# TRV_MRF49_U_V1_1_F.net
KiCad netlist of a schematic drawn in EAGLE
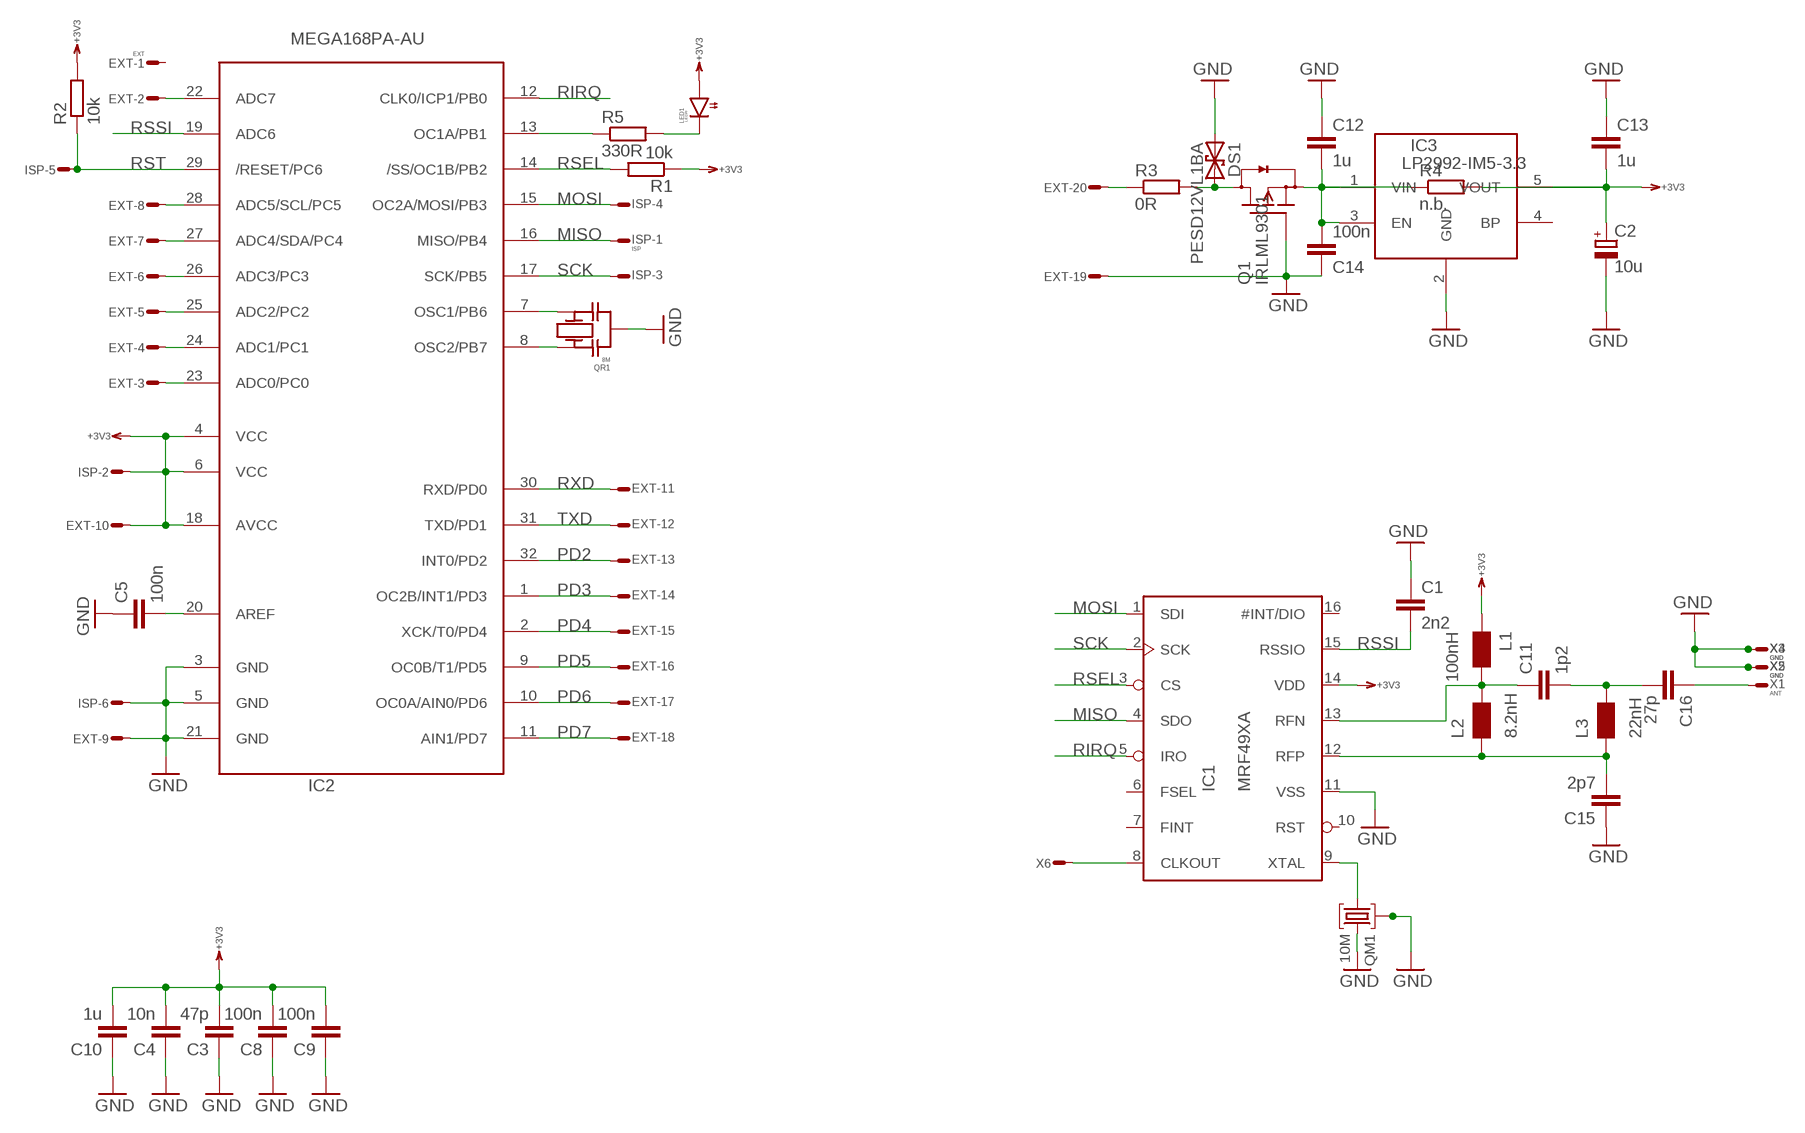
[diagram p0: schematic, sheet 1]

(export (version "E")
  (design (tool "Eeschema 10.0.6"))
  (components
    (comp (ref "C1")
      (value "2n2")
      (footprint "eagle-import:0603")
      (libsource (lib "eagle-import") (part "C0603"))
    )
    (comp (ref "C2")
      (value "10u")
      (footprint "eagle-import:SMC_B")
      (libsource (lib "eagle-import") (part "C_POLSMCB"))
    )
    (comp (ref "C3")
      (value "47p")
      (footprint "eagle-import:0603")
      (libsource (lib "eagle-import") (part "C0603"))
    )
    (comp (ref "C4")
      (value "10n")
      (footprint "eagle-import:0603")
      (libsource (lib "eagle-import") (part "C0603"))
    )
    (comp (ref "C5")
      (value "100n")
      (footprint "eagle-import:0603")
      (libsource (lib "eagle-import") (part "C0603"))
    )
    (comp (ref "C8")
      (value "100n")
      (footprint "eagle-import:0603")
      (libsource (lib "eagle-import") (part "C0603"))
    )
    (comp (ref "C9")
      (value "100n")
      (footprint "eagle-import:0603")
      (libsource (lib "eagle-import") (part "C0603"))
    )
    (comp (ref "C10")
      (value "1u")
      (footprint "eagle-import:0603")
      (libsource (lib "eagle-import") (part "C0603"))
    )
    (comp (ref "C11")
      (value "1p2")
      (footprint "eagle-import:0603")
      (libsource (lib "eagle-import") (part "C0603"))
    )
    (comp (ref "C12")
      (value "1u")
      (footprint "eagle-import:0603")
      (libsource (lib "eagle-import") (part "C0603"))
    )
    (comp (ref "C13")
      (value "1u")
      (footprint "eagle-import:0603")
      (libsource (lib "eagle-import") (part "C0603"))
    )
    (comp (ref "C14")
      (value "100n")
      (footprint "eagle-import:0603")
      (libsource (lib "eagle-import") (part "C0603"))
    )
    (comp (ref "C15")
      (value "2p7")
      (footprint "eagle-import:0603")
      (libsource (lib "eagle-import") (part "C0603"))
    )
    (comp (ref "C16")
      (value "27p")
      (footprint "eagle-import:0603")
      (libsource (lib "eagle-import") (part "C0603"))
    )
    (comp (ref "DS1")
      (value "PESD12VL1BA")
      (footprint "eagle-import:SOD323")
      (libsource (lib "eagle-import") (part "TVS-U323"))
    )
    (comp (ref "EXT")
      (value "EXT")
      (footprint "eagle-import:ML20S")
      (libsource (lib "eagle-import") (part "ML20?ES"))
    )
    (comp (ref "IC1")
      (value "MRF49XA")
      (footprint "eagle-import:TSSOP16")
      (libsource (lib "eagle-import") (part "MRF49XA"))
    )
    (comp (ref "IC2")
      (value "MEGA168PA-AU")
      (footprint "eagle-import:TQFP32-08")
      (libsource (lib "eagle-import") (part "MEGA168PA"))
    )
    (comp (ref "IC3")
      (value "LP2992-IM5-3.3")
      (footprint "eagle-import:SOT23-5")
      (libsource (lib "eagle-import") (part "LDO"))
    )
    (comp (ref "ISP")
      (value "ISP")
      (footprint "eagle-import:ML6S")
      (libsource (lib "eagle-import") (part "ML6ES"))
    )
    (comp (ref "L1")
      (value "100nH")
      (footprint "eagle-import:0603")
      (libsource (lib "eagle-import") (part "L0603"))
    )
    (comp (ref "L2")
      (value "8.2nH")
      (footprint "eagle-import:0603")
      (libsource (lib "eagle-import") (part "L0603"))
    )
    (comp (ref "L3")
      (value "22nH")
      (footprint "eagle-import:0603")
      (libsource (lib "eagle-import") (part "L0603"))
    )
    (comp (ref "LED1")
      (value "LEDR")
      (footprint "eagle-import:0603")
      (libsource (lib "eagle-import") (part "LED0603"))
    )
    (comp (ref "Q1")
      (value "IRLML9301")
      (footprint "eagle-import:SOT23")
      (libsource (lib "eagle-import") (part "FET-PDSOT23"))
    )
    (comp (ref "QM1")
      (value "10M")
      (footprint "eagle-import:ABM3C")
      (libsource (lib "eagle-import") (part "QM5X3.2"))
    )
    (comp (ref "QR1")
      (value "8M")
      (footprint "eagle-import:CR")
      (libsource (lib "eagle-import") (part "QRCR"))
    )
    (comp (ref "R1")
      (value "10k")
      (footprint "eagle-import:0603")
      (libsource (lib "eagle-import") (part "R0603"))
    )
    (comp (ref "R2")
      (value "10k")
      (footprint "eagle-import:0603")
      (libsource (lib "eagle-import") (part "R0603"))
    )
    (comp (ref "R3")
      (value "0R")
      (footprint "eagle-import:0603")
      (libsource (lib "eagle-import") (part "R0603"))
    )
    (comp (ref "R4")
      (value "n.b.")
      (footprint "eagle-import:0603")
      (libsource (lib "eagle-import") (part "R0603"))
    )
    (comp (ref "R5")
      (value "330R")
      (footprint "eagle-import:0603")
      (libsource (lib "eagle-import") (part "R0603"))
    )
    (comp (ref "X1")
      (value "ANT")
      (footprint "eagle-import:S2.54_1.27")
      (libsource (lib "eagle-import") (part "WIREPADS2.54/1.27"))
    )
    (comp (ref "X2")
      (value "GND")
      (footprint "eagle-import:S2.54_1.27")
      (libsource (lib "eagle-import") (part "WIREPADS2.54/1.27"))
    )
    (comp (ref "X3")
      (value "GND")
      (footprint "eagle-import:S2.54_1.27")
      (libsource (lib "eagle-import") (part "WIREPADS2.54/1.27"))
    )
    (comp (ref "X4")
      (value "GND")
      (footprint "eagle-import:S2.54_1.27")
      (libsource (lib "eagle-import") (part "WIREPADS2.54/1.27"))
    )
    (comp (ref "X5")
      (value "GND")
      (footprint "eagle-import:S2.54_1.27")
      (libsource (lib "eagle-import") (part "WIREPADS2.54/1.27"))
    )
    (comp (ref "X6")
      (value "WIREPADR")
      (footprint "eagle-import:S1.27R")
      (libsource (lib "eagle-import") (part "WIREPADR"))
    )
  )
  (nets
    (net (code "1") (name "+3V3") (class "Default")
      (node (ref "C10") (pin "2") (pinfunction "2_2") (pintype "passive"))
      (node (ref "C13") (pin "2") (pinfunction "2_2") (pintype "passive"))
      (node (ref "C2") (pin "+") (pinfunction "+_+") (pintype "passive"))
      (node (ref "C3") (pin "2") (pinfunction "2_2") (pintype "passive"))
      (node (ref "C4") (pin "2") (pinfunction "2_2") (pintype "passive"))
      (node (ref "C8") (pin "2") (pinfunction "2_2") (pintype "passive"))
      (node (ref "C9") (pin "2") (pinfunction "2_2") (pintype "passive"))
      (node (ref "EXT") (pin "10") (pinfunction "S_10") (pintype "passive"))
      (node (ref "IC1") (pin "14") (pinfunction "VDD_14") (pintype "input"))
      (node (ref "IC2") (pin "18") (pinfunction "AVCC_18") (pintype "bidirectional"))
      (node (ref "IC2") (pin "4") (pinfunction "VCC_4") (pintype "bidirectional"))
      (node (ref "IC2") (pin "6") (pinfunction "VCC_6") (pintype "bidirectional"))
      (node (ref "IC3") (pin "5") (pinfunction "VOUT_5") (pintype "bidirectional"))
      (node (ref "ISP") (pin "2") (pinfunction "S_2") (pintype "passive"))
      (node (ref "L1") (pin "1") (pinfunction "1_1") (pintype "passive"))
      (node (ref "LED1") (pin "1") (pinfunction "A_1") (pintype "bidirectional"))
      (node (ref "R1") (pin "1") (pinfunction "1_1") (pintype "passive"))
      (node (ref "R2") (pin "2") (pinfunction "2_2") (pintype "passive"))
      (node (ref "R4") (pin "2") (pinfunction "2_2") (pintype "passive"))
    )
    (net (code "2") (name "/MISO") (class "Default")
      (node (ref "IC1") (pin "4") (pinfunction "SDO_4") (pintype "output"))
      (node (ref "IC2") (pin "16") (pinfunction "MISO/PB4_16") (pintype "bidirectional"))
      (node (ref "ISP") (pin "1") (pinfunction "S_1") (pintype "passive"))
    )
    (net (code "3") (name "/MOSI") (class "Default")
      (node (ref "IC1") (pin "1") (pinfunction "SDI_1") (pintype "input"))
      (node (ref "IC2") (pin "15") (pinfunction "OC2A/MOSI/PB3_15") (pintype "bidirectional"))
      (node (ref "ISP") (pin "4") (pinfunction "S_4") (pintype "passive"))
    )
    (net (code "4") (name "/PD2") (class "Default")
      (node (ref "EXT") (pin "13") (pinfunction "S_13") (pintype "passive"))
      (node (ref "IC2") (pin "32") (pinfunction "INT0/PD2_32") (pintype "bidirectional"))
    )
    (net (code "5") (name "/PD3") (class "Default")
      (node (ref "EXT") (pin "14") (pinfunction "S_14") (pintype "passive"))
      (node (ref "IC2") (pin "1") (pinfunction "OC2B/INT1/PD3_1") (pintype "bidirectional"))
    )
    (net (code "6") (name "/PD4") (class "Default")
      (node (ref "EXT") (pin "15") (pinfunction "S_15") (pintype "passive"))
      (node (ref "IC2") (pin "2") (pinfunction "XCK/T0/PD4_2") (pintype "bidirectional"))
    )
    (net (code "7") (name "/PD5") (class "Default")
      (node (ref "EXT") (pin "16") (pinfunction "S_16") (pintype "passive"))
      (node (ref "IC2") (pin "9") (pinfunction "OC0B/T1/PD5_9") (pintype "bidirectional"))
    )
    (net (code "8") (name "/PD6") (class "Default")
      (node (ref "EXT") (pin "17") (pinfunction "S_17") (pintype "passive"))
      (node (ref "IC2") (pin "10") (pinfunction "OC0A/AIN0/PD6_10") (pintype "bidirectional"))
    )
    (net (code "9") (name "/PD7") (class "Default")
      (node (ref "EXT") (pin "18") (pinfunction "S_18") (pintype "passive"))
      (node (ref "IC2") (pin "11") (pinfunction "AIN1/PD7_11") (pintype "bidirectional"))
    )
    (net (code "10") (name "/RIRQ") (class "Default")
      (node (ref "IC1") (pin "5") (pinfunction "IRO_5") (pintype "output"))
      (node (ref "IC2") (pin "12") (pinfunction "CLK0/ICP1/PB0_12") (pintype "bidirectional"))
    )
    (net (code "11") (name "/RSEL") (class "Default")
      (node (ref "IC1") (pin "3") (pinfunction "CS_3") (pintype "input"))
      (node (ref "IC2") (pin "14") (pinfunction "/SS/OC1B/PB2_14") (pintype "bidirectional"))
      (node (ref "R1") (pin "2") (pinfunction "2_2") (pintype "passive"))
    )
    (net (code "12") (name "/RSSI") (class "Default")
      (node (ref "C1") (pin "2") (pinfunction "2_2") (pintype "passive"))
      (node (ref "IC1") (pin "15") (pinfunction "RSSIO_15") (pintype "bidirectional"))
      (node (ref "IC2") (pin "19") (pinfunction "ADC6_19") (pintype "bidirectional"))
    )
    (net (code "13") (name "/RST") (class "Default")
      (node (ref "IC2") (pin "29") (pinfunction "/RESET/PC6_29") (pintype "bidirectional"))
      (node (ref "ISP") (pin "5") (pinfunction "S_5") (pintype "passive"))
      (node (ref "R2") (pin "1") (pinfunction "1_1") (pintype "passive"))
    )
    (net (code "14") (name "/RXD") (class "Default")
      (node (ref "EXT") (pin "11") (pinfunction "S_11") (pintype "passive"))
      (node (ref "IC2") (pin "30") (pinfunction "RXD/PD0_30") (pintype "bidirectional"))
    )
    (net (code "15") (name "/SCK") (class "Default")
      (node (ref "IC1") (pin "2") (pinfunction "SCK_2") (pintype "input"))
      (node (ref "IC2") (pin "17") (pinfunction "SCK/PB5_17") (pintype "bidirectional"))
      (node (ref "ISP") (pin "3") (pinfunction "S_3") (pintype "passive"))
    )
    (net (code "16") (name "/TXD") (class "Default")
      (node (ref "EXT") (pin "12") (pinfunction "S_12") (pintype "passive"))
      (node (ref "IC2") (pin "31") (pinfunction "TXD/PD1_31") (pintype "bidirectional"))
    )
    (net (code "17") (name "GND") (class "Default")
      (node (ref "C1") (pin "1") (pinfunction "1_1") (pintype "passive"))
      (node (ref "C10") (pin "1") (pinfunction "1_1") (pintype "passive"))
      (node (ref "C12") (pin "1") (pinfunction "1_1") (pintype "passive"))
      (node (ref "C13") (pin "1") (pinfunction "1_1") (pintype "passive"))
      (node (ref "C14") (pin "1") (pinfunction "1_1") (pintype "passive"))
      (node (ref "C15") (pin "1") (pinfunction "1_1") (pintype "passive"))
      (node (ref "C2") (pin "-") (pinfunction "-_-") (pintype "passive"))
      (node (ref "C3") (pin "1") (pinfunction "1_1") (pintype "passive"))
      (node (ref "C4") (pin "1") (pinfunction "1_1") (pintype "passive"))
      (node (ref "C5") (pin "1") (pinfunction "1_1") (pintype "passive"))
      (node (ref "C8") (pin "1") (pinfunction "1_1") (pintype "passive"))
      (node (ref "C9") (pin "1") (pinfunction "1_1") (pintype "passive"))
      (node (ref "DS1") (pin "A") (pinfunction "1_A") (pintype "passive"))
      (node (ref "EXT") (pin "19") (pinfunction "S_19") (pintype "passive"))
      (node (ref "EXT") (pin "9") (pinfunction "S_9") (pintype "passive"))
      (node (ref "IC1") (pin "11") (pinfunction "VSS_11") (pintype "input"))
      (node (ref "IC2") (pin "21") (pinfunction "GND_21") (pintype "bidirectional"))
      (node (ref "IC2") (pin "3") (pinfunction "GND_3") (pintype "bidirectional"))
      (node (ref "IC2") (pin "5") (pinfunction "GND_5") (pintype "bidirectional"))
      (node (ref "IC3") (pin "2") (pinfunction "GND_2") (pintype "bidirectional"))
      (node (ref "ISP") (pin "6") (pinfunction "S_6") (pintype "passive"))
      (node (ref "Q1") (pin "1") (pinfunction "G_1") (pintype "passive"))
      (node (ref "QM1") (pin "P$2") (pinfunction "M1_P$2") (pintype "passive"))
      (node (ref "QM1") (pin "P$3") (pinfunction "2_P$3") (pintype "passive"))
      (node (ref "QM1") (pin "P$4") (pinfunction "M2_P$4") (pintype "passive"))
      (node (ref "QR1") (pin "M") (pinfunction "M_M") (pintype "passive"))
      (node (ref "X2") (pin "1") (pinfunction "S_1") (pintype "passive"))
      (node (ref "X3") (pin "1") (pinfunction "S_1") (pintype "passive"))
      (node (ref "X4") (pin "1") (pinfunction "S_1") (pintype "passive"))
      (node (ref "X5") (pin "1") (pinfunction "S_1") (pintype "passive"))
    )
    (net (code "18") (name "Net-(C11-Pad2)") (class "Default")
      (node (ref "C11") (pin "2") (pinfunction "2_2") (pintype "passive"))
      (node (ref "C16") (pin "2") (pinfunction "2_2") (pintype "passive"))
      (node (ref "L3") (pin "2") (pinfunction "2_2") (pintype "passive"))
    )
    (net (code "19") (name "Net-(DS1-2)") (class "Default")
      (node (ref "DS1") (pin "C") (pinfunction "2_C") (pintype "passive"))
      (node (ref "Q1") (pin "3") (pinfunction "D_3") (pintype "passive"))
      (node (ref "R3") (pin "2") (pinfunction "2_2") (pintype "passive"))
    )
    (net (code "20") (name "Net-(EXTL-S)") (class "Default")
      (node (ref "EXT") (pin "2") (pinfunction "S_2") (pintype "passive"))
      (node (ref "IC2") (pin "22") (pinfunction "ADC7_22") (pintype "bidirectional"))
    )
    (net (code "21") (name "Net-(EXTM-S)") (class "Default")
      (node (ref "EXT") (pin "20") (pinfunction "S_20") (pintype "passive"))
      (node (ref "R3") (pin "1") (pinfunction "1_1") (pintype "passive"))
    )
    (net (code "22") (name "Net-(EXTN-S)") (class "Default")
      (node (ref "EXT") (pin "3") (pinfunction "S_3") (pintype "passive"))
      (node (ref "IC2") (pin "23") (pinfunction "ADC0/PC0_23") (pintype "bidirectional"))
    )
    (net (code "23") (name "Net-(EXTO-S)") (class "Default")
      (node (ref "EXT") (pin "4") (pinfunction "S_4") (pintype "passive"))
      (node (ref "IC2") (pin "24") (pinfunction "ADC1/PC1_24") (pintype "bidirectional"))
    )
    (net (code "24") (name "Net-(EXTP-S)") (class "Default")
      (node (ref "EXT") (pin "5") (pinfunction "S_5") (pintype "passive"))
      (node (ref "IC2") (pin "25") (pinfunction "ADC2/PC2_25") (pintype "bidirectional"))
    )
    (net (code "25") (name "Net-(EXTQ-S)") (class "Default")
      (node (ref "EXT") (pin "6") (pinfunction "S_6") (pintype "passive"))
      (node (ref "IC2") (pin "26") (pinfunction "ADC3/PC3_26") (pintype "bidirectional"))
    )
    (net (code "26") (name "Net-(EXTR-S)") (class "Default")
      (node (ref "EXT") (pin "7") (pinfunction "S_7") (pintype "passive"))
      (node (ref "IC2") (pin "27") (pinfunction "ADC4/SDA/PC4_27") (pintype "bidirectional"))
    )
    (net (code "27") (name "Net-(EXTS-S)") (class "Default")
      (node (ref "EXT") (pin "8") (pinfunction "S_8") (pintype "passive"))
      (node (ref "IC2") (pin "28") (pinfunction "ADC5/SCL/PC5_28") (pintype "bidirectional"))
    )
    (net (code "28") (name "Net-(IC1-CLKOUT)") (class "Default")
      (node (ref "IC1") (pin "8") (pinfunction "CLKOUT_8") (pintype "output"))
      (node (ref "X6") (pin "1") (pinfunction "S_1") (pintype "passive"))
    )
    (net (code "29") (name "Net-(IC1-RFN)") (class "Default")
      (node (ref "C11") (pin "1") (pinfunction "1_1") (pintype "passive"))
      (node (ref "IC1") (pin "13") (pinfunction "RFN_13") (pintype "bidirectional"))
      (node (ref "L1") (pin "2") (pinfunction "2_2") (pintype "passive"))
      (node (ref "L2") (pin "2") (pinfunction "2_2") (pintype "passive"))
    )
    (net (code "30") (name "Net-(IC1-RFP)") (class "Default")
      (node (ref "C15") (pin "2") (pinfunction "2_2") (pintype "passive"))
      (node (ref "IC1") (pin "12") (pinfunction "RFP_12") (pintype "bidirectional"))
      (node (ref "L2") (pin "1") (pinfunction "1_1") (pintype "passive"))
      (node (ref "L3") (pin "1") (pinfunction "1_1") (pintype "passive"))
    )
    (net (code "31") (name "Net-(IC1-XTAL)") (class "Default")
      (node (ref "IC1") (pin "9") (pinfunction "XTAL_9") (pintype "input"))
      (node (ref "QM1") (pin "P$1") (pinfunction "1_P$1") (pintype "passive"))
    )
    (net (code "32") (name "Net-(IC2-AREF)") (class "Default")
      (node (ref "C5") (pin "2") (pinfunction "2_2") (pintype "passive"))
      (node (ref "IC2") (pin "20") (pinfunction "AREF_20") (pintype "bidirectional"))
    )
    (net (code "33") (name "Net-(IC2-OC1A{slash}PB1)") (class "Default")
      (node (ref "IC2") (pin "13") (pinfunction "OC1A/PB1_13") (pintype "bidirectional"))
      (node (ref "R5") (pin "1") (pinfunction "1_1") (pintype "passive"))
    )
    (net (code "34") (name "Net-(IC2-OSC1{slash}PB6)") (class "Default")
      (node (ref "IC2") (pin "7") (pinfunction "OSC1/PB6_7") (pintype "bidirectional"))
      (node (ref "QR1") (pin "2") (pinfunction "2_2") (pintype "passive"))
    )
    (net (code "35") (name "Net-(IC2-OSC2{slash}PB7)") (class "Default")
      (node (ref "IC2") (pin "8") (pinfunction "OSC2/PB7_8") (pintype "bidirectional"))
      (node (ref "QR1") (pin "1") (pinfunction "1_1") (pintype "passive"))
    )
    (net (code "36") (name "Net-(IC3-EN)") (class "Default")
      (node (ref "C12") (pin "2") (pinfunction "2_2") (pintype "passive"))
      (node (ref "C14") (pin "2") (pinfunction "2_2") (pintype "passive"))
      (node (ref "IC3") (pin "1") (pinfunction "VIN_1") (pintype "bidirectional"))
      (node (ref "IC3") (pin "3") (pinfunction "EN_3") (pintype "bidirectional"))
      (node (ref "Q1") (pin "2") (pinfunction "S_2") (pintype "passive"))
      (node (ref "R4") (pin "1") (pinfunction "1_1") (pintype "passive"))
    )
    (net (code "37") (name "Net-(LED1-C)") (class "Default")
      (node (ref "LED1") (pin "2") (pinfunction "C_2") (pintype "bidirectional"))
      (node (ref "R5") (pin "2") (pinfunction "2_2") (pintype "passive"))
    )
    (net (code "38") (name "Net-(X1-S)") (class "Default")
      (node (ref "C16") (pin "1") (pinfunction "1_1") (pintype "passive"))
      (node (ref "X1") (pin "1") (pinfunction "S_1") (pintype "passive"))
    )
    (net (code "39") (name "unconnected-(EXTA-S-Pad1)") (class "Default")
      (node (ref "EXT") (pin "1") (pinfunction "S_1") (pintype "passive"))
    )
    (net (code "40") (name "unconnected-(IC1-#INT{slash}DIO-Pad16)") (class "Default")
      (node (ref "IC1") (pin "16") (pinfunction "#INT/DIO_16") (pintype "bidirectional"))
    )
    (net (code "41") (name "unconnected-(IC1-FINT-Pad7)") (class "Default")
      (node (ref "IC1") (pin "7") (pinfunction "FINT_7") (pintype "bidirectional"))
    )
    (net (code "42") (name "unconnected-(IC1-FSEL-Pad6)") (class "Default")
      (node (ref "IC1") (pin "6") (pinfunction "FSEL_6") (pintype "bidirectional"))
    )
    (net (code "43") (name "unconnected-(IC1-RST-Pad10)") (class "Default")
      (node (ref "IC1") (pin "10") (pinfunction "RST_10") (pintype "bidirectional"))
    )
    (net (code "44") (name "unconnected-(IC3-BP-Pad4)") (class "Default")
      (node (ref "IC3") (pin "4") (pinfunction "BP_4") (pintype "bidirectional"))
    )
  )
)
